# PhoenicianClock_d.net
KiCad netlist of a schematic drawn in EAGLE
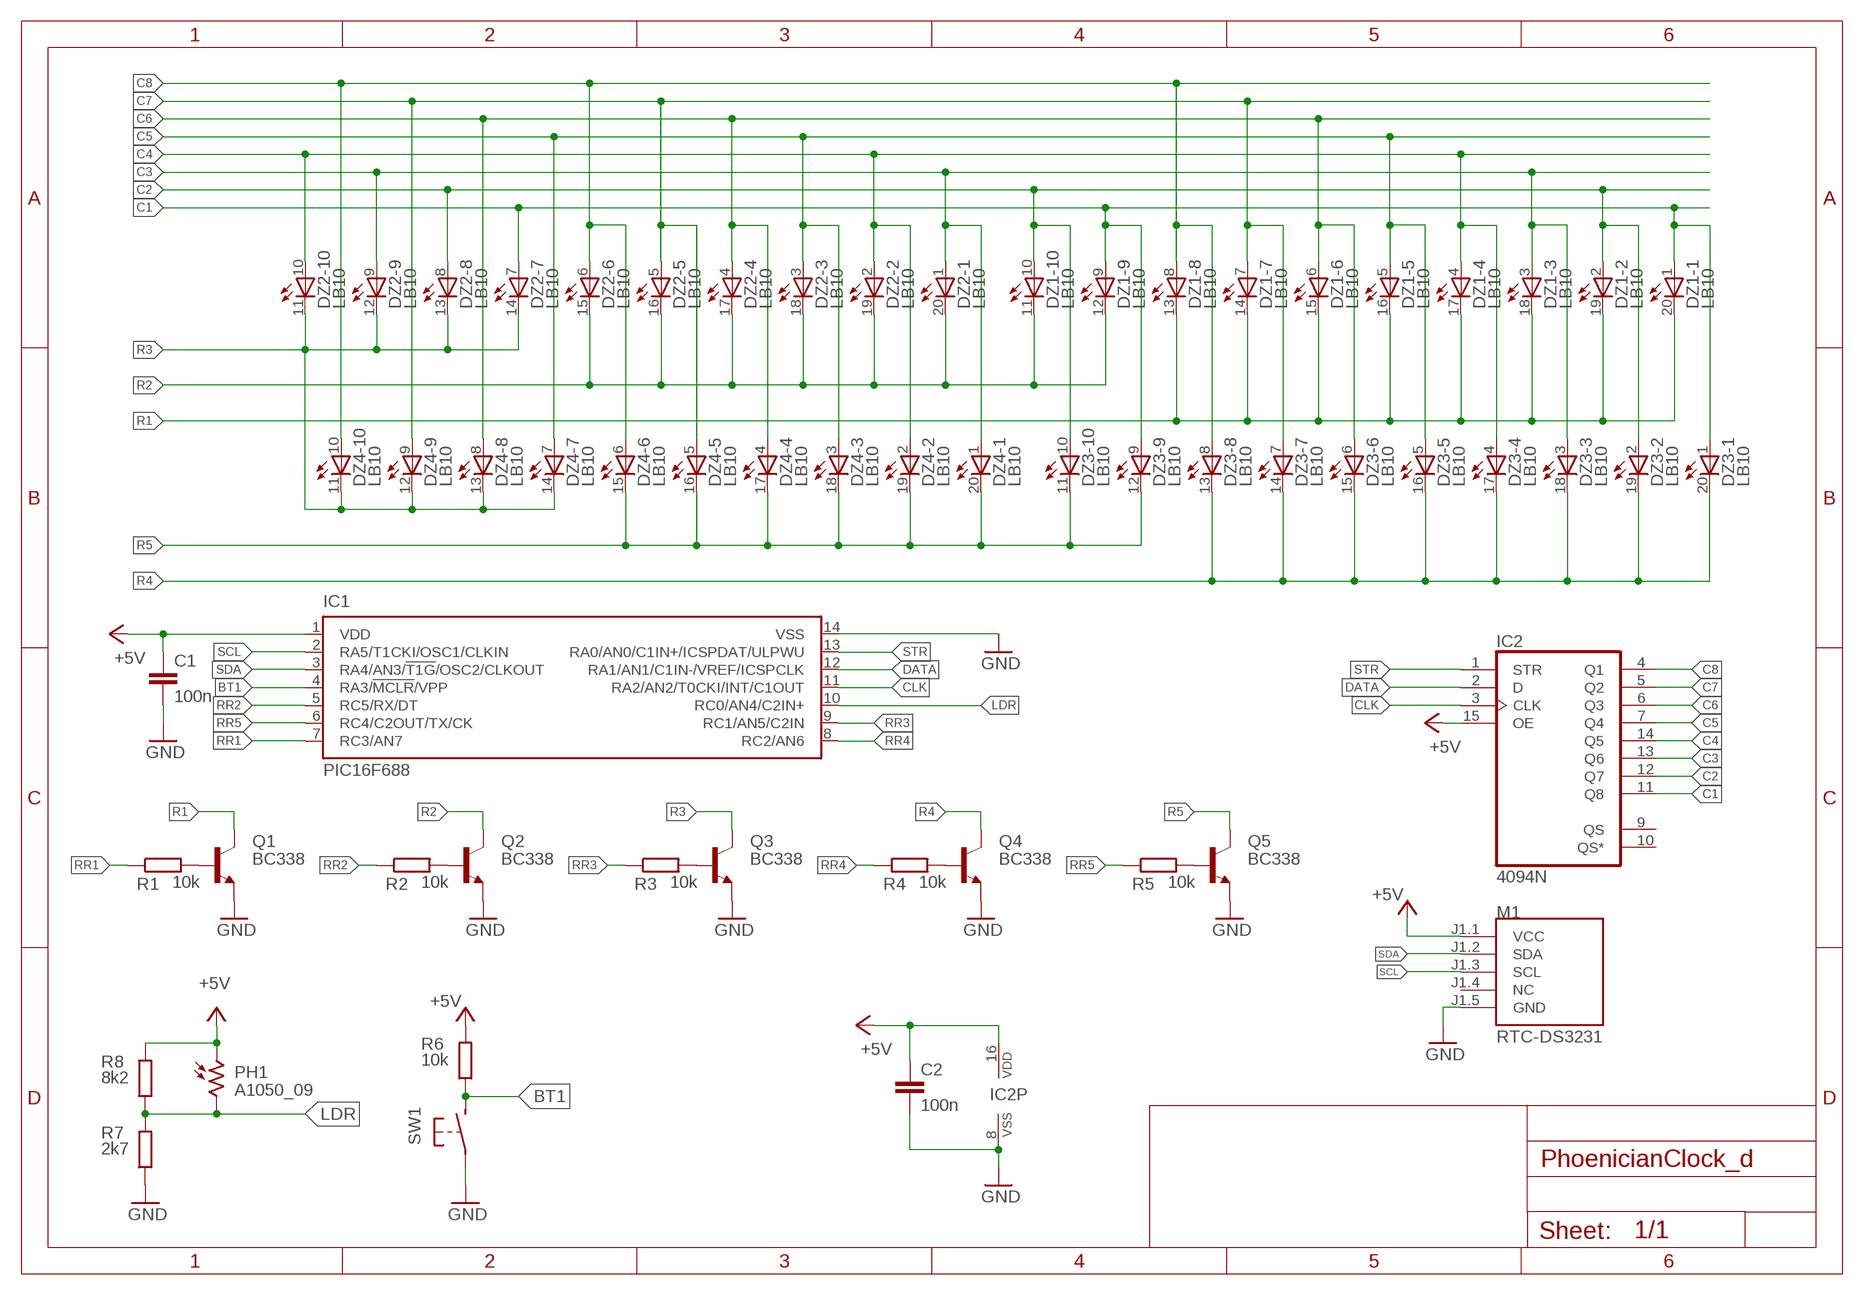
[diagram p0: schematic, sheet 1]

(export (version "E")
  (design (tool "Eeschema 10.0.6"))
  (components
    (comp (ref "C1")
      (value "100n")
      (footprint "eagle-import:C050-024X044")
      (libsource (lib "eagle-import") (part "C-EU050-024X044"))
    )
    (comp (ref "C2")
      (value "100n")
      (footprint "eagle-import:C050-024X044")
      (libsource (lib "eagle-import") (part "C-EU050-024X044"))
    )
    (comp (ref "DZ1")
      (value "LB10")
      (footprint "eagle-import:LB10")
      (libsource (lib "eagle-import") (part "LB10"))
    )
    (comp (ref "DZ2")
      (value "LB10")
      (footprint "eagle-import:LB10")
      (libsource (lib "eagle-import") (part "LB10"))
    )
    (comp (ref "DZ3")
      (value "LB10")
      (footprint "eagle-import:LB10")
      (libsource (lib "eagle-import") (part "LB10"))
    )
    (comp (ref "DZ4")
      (value "LB10")
      (footprint "eagle-import:LB10")
      (libsource (lib "eagle-import") (part "LB10"))
    )
    (comp (ref "IC1")
      (value "PIC16F688")
      (footprint "eagle-import:DIL14")
      (libsource (lib "eagle-import") (part "PIC16F688"))
    )
    (comp (ref "IC2")
      (value "4094N")
      (footprint "eagle-import:DIL16")
      (libsource (lib "eagle-import") (part "4094N"))
    )
    (comp (ref "M1")
      (value "RTC-DS3231")
      (footprint "eagle-import:RTC-DS3231_SMALL")
      (libsource (lib "eagle-import") (part "RTC-DS3231"))
    )
    (comp (ref "PH1")
      (value "A1050_09")
      (footprint "eagle-import:T0-46-A10XX")
      (libsource (lib "eagle-import") (part "A1050_09"))
    )
    (comp (ref "Q1")
      (value "BC338")
      (footprint "eagle-import:TO92-EBC")
      (libsource (lib "eagle-import") (part "BC338"))
    )
    (comp (ref "Q2")
      (value "BC338")
      (footprint "eagle-import:TO92-EBC")
      (libsource (lib "eagle-import") (part "BC338"))
    )
    (comp (ref "Q3")
      (value "BC338")
      (footprint "eagle-import:TO92-EBC")
      (libsource (lib "eagle-import") (part "BC338"))
    )
    (comp (ref "Q4")
      (value "BC338")
      (footprint "eagle-import:TO92-EBC")
      (libsource (lib "eagle-import") (part "BC338"))
    )
    (comp (ref "Q5")
      (value "BC338")
      (footprint "eagle-import:TO92-EBC")
      (libsource (lib "eagle-import") (part "BC338"))
    )
    (comp (ref "R1")
      (value "10k")
      (footprint "eagle-import:0204_5")
      (libsource (lib "eagle-import") (part "R-EU_0204/5"))
    )
    (comp (ref "R2")
      (value "10k")
      (footprint "eagle-import:0204_5")
      (libsource (lib "eagle-import") (part "R-EU_0204/5"))
    )
    (comp (ref "R3")
      (value "10k")
      (footprint "eagle-import:0204_5")
      (libsource (lib "eagle-import") (part "R-EU_0204/5"))
    )
    (comp (ref "R4")
      (value "10k")
      (footprint "eagle-import:0204_5")
      (libsource (lib "eagle-import") (part "R-EU_0204/5"))
    )
    (comp (ref "R5")
      (value "10k")
      (footprint "eagle-import:0204_5")
      (libsource (lib "eagle-import") (part "R-EU_0204/5"))
    )
    (comp (ref "R6")
      (value "10k")
      (footprint "eagle-import:0204_5")
      (libsource (lib "eagle-import") (part "R-EU_0204/5"))
    )
    (comp (ref "R7")
      (value "2k7")
      (footprint "eagle-import:0204_5")
      (libsource (lib "eagle-import") (part "R-EU_0204/5"))
    )
    (comp (ref "R8")
      (value "8k2")
      (footprint "eagle-import:0204_5")
      (libsource (lib "eagle-import") (part "R-EU_0204/5"))
    )
    (comp (ref "SW1")
      (value "MINISPDT")
      (footprint "eagle-import:2PST_MINI")
      (libsource (lib "eagle-import") (part "MINISPDT"))
    )
  )
  (nets
    (net (code "1") (name "+5V") (class "Default")
      (node (ref "C1") (pin "1") (pinfunction "1_1") (pintype "passive"))
      (node (ref "C2") (pin "1") (pinfunction "1_1") (pintype "passive"))
      (node (ref "IC1") (pin "1") (pinfunction "VDD_1") (pintype "power_in"))
      (node (ref "IC2") (pin "15") (pinfunction "OE_15") (pintype "input"))
      (node (ref "IC2") (pin "16") (pinfunction "VDD_16") (pintype "power_in"))
      (node (ref "M1") (pin "J1.1") (pinfunction "VCC_J1.1") (pintype "power_in"))
      (node (ref "PH1") (pin "1") (pinfunction "1_1") (pintype "passive"))
      (node (ref "R6") (pin "2") (pinfunction "2_2") (pintype "passive"))
      (node (ref "R8") (pin "2") (pinfunction "2_2") (pintype "passive"))
    )
    (net (code "2") (name "BT1") (class "Default")
      (node (ref "IC1") (pin "4") (pinfunction "RA3/~{MCLR}/VPP_4") (pintype "bidirectional"))
      (node (ref "R6") (pin "1") (pinfunction "1_1") (pintype "passive"))
      (node (ref "SW1") (pin "P$2") (pinfunction "S_P$2") (pintype "passive"))
    )
    (net (code "3") (name "C1") (class "Default")
      (node (ref "DZ1") (pin "1") (pinfunction "A_1") (pintype "passive"))
      (node (ref "DZ1") (pin "9") (pinfunction "A_9") (pintype "passive"))
      (node (ref "DZ2") (pin "7") (pinfunction "A_7") (pintype "passive"))
      (node (ref "DZ3") (pin "1") (pinfunction "A_1") (pintype "passive"))
      (node (ref "DZ3") (pin "9") (pinfunction "A_9") (pintype "passive"))
      (node (ref "IC2") (pin "11") (pinfunction "Q8_11") (pintype "output"))
    )
    (net (code "4") (name "C2") (class "Default")
      (node (ref "DZ1") (pin "10") (pinfunction "A_10") (pintype "passive"))
      (node (ref "DZ1") (pin "2") (pinfunction "A_2") (pintype "passive"))
      (node (ref "DZ2") (pin "8") (pinfunction "A_8") (pintype "passive"))
      (node (ref "DZ3") (pin "10") (pinfunction "A_10") (pintype "passive"))
      (node (ref "DZ3") (pin "2") (pinfunction "A_2") (pintype "passive"))
      (node (ref "IC2") (pin "12") (pinfunction "Q7_12") (pintype "output"))
    )
    (net (code "5") (name "C3") (class "Default")
      (node (ref "DZ1") (pin "3") (pinfunction "A_3") (pintype "passive"))
      (node (ref "DZ2") (pin "1") (pinfunction "A_1") (pintype "passive"))
      (node (ref "DZ2") (pin "9") (pinfunction "A_9") (pintype "passive"))
      (node (ref "DZ3") (pin "3") (pinfunction "A_3") (pintype "passive"))
      (node (ref "DZ4") (pin "1") (pinfunction "A_1") (pintype "passive"))
      (node (ref "IC2") (pin "13") (pinfunction "Q6_13") (pintype "output"))
    )
    (net (code "6") (name "C4") (class "Default")
      (node (ref "DZ1") (pin "4") (pinfunction "A_4") (pintype "passive"))
      (node (ref "DZ2") (pin "10") (pinfunction "A_10") (pintype "passive"))
      (node (ref "DZ2") (pin "2") (pinfunction "A_2") (pintype "passive"))
      (node (ref "DZ3") (pin "4") (pinfunction "A_4") (pintype "passive"))
      (node (ref "DZ4") (pin "2") (pinfunction "A_2") (pintype "passive"))
      (node (ref "IC2") (pin "14") (pinfunction "Q5_14") (pintype "output"))
    )
    (net (code "7") (name "C5") (class "Default")
      (node (ref "DZ1") (pin "5") (pinfunction "A_5") (pintype "passive"))
      (node (ref "DZ2") (pin "3") (pinfunction "A_3") (pintype "passive"))
      (node (ref "DZ3") (pin "5") (pinfunction "A_5") (pintype "passive"))
      (node (ref "DZ4") (pin "3") (pinfunction "A_3") (pintype "passive"))
      (node (ref "DZ4") (pin "7") (pinfunction "A_7") (pintype "passive"))
      (node (ref "IC2") (pin "7") (pinfunction "Q4_7") (pintype "output"))
    )
    (net (code "8") (name "C6") (class "Default")
      (node (ref "DZ1") (pin "6") (pinfunction "A_6") (pintype "passive"))
      (node (ref "DZ2") (pin "4") (pinfunction "A_4") (pintype "passive"))
      (node (ref "DZ3") (pin "6") (pinfunction "A_6") (pintype "passive"))
      (node (ref "DZ4") (pin "4") (pinfunction "A_4") (pintype "passive"))
      (node (ref "DZ4") (pin "8") (pinfunction "A_8") (pintype "passive"))
      (node (ref "IC2") (pin "6") (pinfunction "Q3_6") (pintype "output"))
    )
    (net (code "9") (name "C7") (class "Default")
      (node (ref "DZ1") (pin "7") (pinfunction "A_7") (pintype "passive"))
      (node (ref "DZ2") (pin "5") (pinfunction "A_5") (pintype "passive"))
      (node (ref "DZ3") (pin "7") (pinfunction "A_7") (pintype "passive"))
      (node (ref "DZ4") (pin "5") (pinfunction "A_5") (pintype "passive"))
      (node (ref "DZ4") (pin "9") (pinfunction "A_9") (pintype "passive"))
      (node (ref "IC2") (pin "5") (pinfunction "Q2_5") (pintype "output"))
    )
    (net (code "10") (name "C8") (class "Default")
      (node (ref "DZ1") (pin "8") (pinfunction "A_8") (pintype "passive"))
      (node (ref "DZ2") (pin "6") (pinfunction "A_6") (pintype "passive"))
      (node (ref "DZ3") (pin "8") (pinfunction "A_8") (pintype "passive"))
      (node (ref "DZ4") (pin "10") (pinfunction "A_10") (pintype "passive"))
      (node (ref "DZ4") (pin "6") (pinfunction "A_6") (pintype "passive"))
      (node (ref "IC2") (pin "4") (pinfunction "Q1_4") (pintype "output"))
    )
    (net (code "11") (name "CLK") (class "Default")
      (node (ref "IC1") (pin "11") (pinfunction "RA2/AN2/T0CKI/INT/C1OUT_11") (pintype "bidirectional"))
      (node (ref "IC2") (pin "3") (pinfunction "CLK_3") (pintype "input"))
    )
    (net (code "12") (name "DATA") (class "Default")
      (node (ref "IC1") (pin "12") (pinfunction "RA1/AN1/C1IN-/VREF/ICSPCLK_12") (pintype "bidirectional"))
      (node (ref "IC2") (pin "2") (pinfunction "D_2") (pintype "input"))
    )
    (net (code "13") (name "GND") (class "Default")
      (node (ref "C1") (pin "2") (pinfunction "2_2") (pintype "passive"))
      (node (ref "C2") (pin "2") (pinfunction "2_2") (pintype "passive"))
      (node (ref "IC1") (pin "14") (pinfunction "VSS_14") (pintype "power_in"))
      (node (ref "IC2") (pin "8") (pinfunction "VSS_8") (pintype "power_in"))
      (node (ref "M1") (pin "J1.5") (pinfunction "GND_J1.5") (pintype "power_in"))
      (node (ref "Q1") (pin "E") (pinfunction "E_E") (pintype "passive"))
      (node (ref "Q2") (pin "E") (pinfunction "E_E") (pintype "passive"))
      (node (ref "Q3") (pin "E") (pinfunction "E_E") (pintype "passive"))
      (node (ref "Q4") (pin "E") (pinfunction "E_E") (pintype "passive"))
      (node (ref "Q5") (pin "E") (pinfunction "E_E") (pintype "passive"))
      (node (ref "R7") (pin "1") (pinfunction "1_1") (pintype "passive"))
      (node (ref "SW1") (pin "P$1") (pinfunction "P_P$1") (pintype "passive"))
    )
    (net (code "14") (name "LDR") (class "Default")
      (node (ref "IC1") (pin "10") (pinfunction "RC0/AN4/C2IN+_10") (pintype "bidirectional"))
      (node (ref "PH1") (pin "2") (pinfunction "2_2") (pintype "passive"))
      (node (ref "R7") (pin "2") (pinfunction "2_2") (pintype "passive"))
      (node (ref "R8") (pin "1") (pinfunction "1_1") (pintype "passive"))
    )
    (net (code "15") (name "Net-(Q1-PadB)") (class "Default")
      (node (ref "Q1") (pin "B") (pinfunction "B_B") (pintype "passive"))
      (node (ref "R1") (pin "2") (pinfunction "2_2") (pintype "passive"))
    )
    (net (code "16") (name "Net-(Q2-PadB)") (class "Default")
      (node (ref "Q2") (pin "B") (pinfunction "B_B") (pintype "passive"))
      (node (ref "R2") (pin "2") (pinfunction "2_2") (pintype "passive"))
    )
    (net (code "17") (name "Net-(Q3-PadB)") (class "Default")
      (node (ref "Q3") (pin "B") (pinfunction "B_B") (pintype "passive"))
      (node (ref "R3") (pin "2") (pinfunction "2_2") (pintype "passive"))
    )
    (net (code "18") (name "Net-(Q4-PadB)") (class "Default")
      (node (ref "Q4") (pin "B") (pinfunction "B_B") (pintype "passive"))
      (node (ref "R4") (pin "2") (pinfunction "2_2") (pintype "passive"))
    )
    (net (code "19") (name "Net-(Q5-PadB)") (class "Default")
      (node (ref "Q5") (pin "B") (pinfunction "B_B") (pintype "passive"))
      (node (ref "R5") (pin "2") (pinfunction "2_2") (pintype "passive"))
    )
    (net (code "20") (name "R1") (class "Default")
      (node (ref "DZ1") (pin "13") (pinfunction "C_13") (pintype "passive"))
      (node (ref "DZ1") (pin "14") (pinfunction "C_14") (pintype "passive"))
      (node (ref "DZ1") (pin "15") (pinfunction "C_15") (pintype "passive"))
      (node (ref "DZ1") (pin "16") (pinfunction "C_16") (pintype "passive"))
      (node (ref "DZ1") (pin "17") (pinfunction "C_17") (pintype "passive"))
      (node (ref "DZ1") (pin "18") (pinfunction "C_18") (pintype "passive"))
      (node (ref "DZ1") (pin "19") (pinfunction "C_19") (pintype "passive"))
      (node (ref "DZ1") (pin "20") (pinfunction "C_20") (pintype "passive"))
      (node (ref "Q1") (pin "C") (pinfunction "C_C") (pintype "passive"))
    )
    (net (code "21") (name "R2") (class "Default")
      (node (ref "DZ1") (pin "11") (pinfunction "C_11") (pintype "passive"))
      (node (ref "DZ1") (pin "12") (pinfunction "C_12") (pintype "passive"))
      (node (ref "DZ2") (pin "15") (pinfunction "C_15") (pintype "passive"))
      (node (ref "DZ2") (pin "16") (pinfunction "C_16") (pintype "passive"))
      (node (ref "DZ2") (pin "17") (pinfunction "C_17") (pintype "passive"))
      (node (ref "DZ2") (pin "18") (pinfunction "C_18") (pintype "passive"))
      (node (ref "DZ2") (pin "19") (pinfunction "C_19") (pintype "passive"))
      (node (ref "DZ2") (pin "20") (pinfunction "C_20") (pintype "passive"))
      (node (ref "Q2") (pin "C") (pinfunction "C_C") (pintype "passive"))
    )
    (net (code "22") (name "R3") (class "Default")
      (node (ref "DZ2") (pin "11") (pinfunction "C_11") (pintype "passive"))
      (node (ref "DZ2") (pin "12") (pinfunction "C_12") (pintype "passive"))
      (node (ref "DZ2") (pin "13") (pinfunction "C_13") (pintype "passive"))
      (node (ref "DZ2") (pin "14") (pinfunction "C_14") (pintype "passive"))
      (node (ref "DZ4") (pin "11") (pinfunction "C_11") (pintype "passive"))
      (node (ref "DZ4") (pin "12") (pinfunction "C_12") (pintype "passive"))
      (node (ref "DZ4") (pin "13") (pinfunction "C_13") (pintype "passive"))
      (node (ref "DZ4") (pin "14") (pinfunction "C_14") (pintype "passive"))
      (node (ref "Q3") (pin "C") (pinfunction "C_C") (pintype "passive"))
    )
    (net (code "23") (name "R4") (class "Default")
      (node (ref "DZ3") (pin "13") (pinfunction "C_13") (pintype "passive"))
      (node (ref "DZ3") (pin "14") (pinfunction "C_14") (pintype "passive"))
      (node (ref "DZ3") (pin "15") (pinfunction "C_15") (pintype "passive"))
      (node (ref "DZ3") (pin "16") (pinfunction "C_16") (pintype "passive"))
      (node (ref "DZ3") (pin "17") (pinfunction "C_17") (pintype "passive"))
      (node (ref "DZ3") (pin "18") (pinfunction "C_18") (pintype "passive"))
      (node (ref "DZ3") (pin "19") (pinfunction "C_19") (pintype "passive"))
      (node (ref "DZ3") (pin "20") (pinfunction "C_20") (pintype "passive"))
      (node (ref "Q4") (pin "C") (pinfunction "C_C") (pintype "passive"))
    )
    (net (code "24") (name "R5") (class "Default")
      (node (ref "DZ3") (pin "11") (pinfunction "C_11") (pintype "passive"))
      (node (ref "DZ3") (pin "12") (pinfunction "C_12") (pintype "passive"))
      (node (ref "DZ4") (pin "15") (pinfunction "C_15") (pintype "passive"))
      (node (ref "DZ4") (pin "16") (pinfunction "C_16") (pintype "passive"))
      (node (ref "DZ4") (pin "17") (pinfunction "C_17") (pintype "passive"))
      (node (ref "DZ4") (pin "18") (pinfunction "C_18") (pintype "passive"))
      (node (ref "DZ4") (pin "19") (pinfunction "C_19") (pintype "passive"))
      (node (ref "DZ4") (pin "20") (pinfunction "C_20") (pintype "passive"))
      (node (ref "Q5") (pin "C") (pinfunction "C_C") (pintype "passive"))
    )
    (net (code "25") (name "RR1") (class "Default")
      (node (ref "IC1") (pin "7") (pinfunction "RC3/AN7_7") (pintype "bidirectional"))
      (node (ref "R1") (pin "1") (pinfunction "1_1") (pintype "passive"))
    )
    (net (code "26") (name "RR2") (class "Default")
      (node (ref "IC1") (pin "5") (pinfunction "RC5/RX/DT_5") (pintype "bidirectional"))
      (node (ref "R2") (pin "1") (pinfunction "1_1") (pintype "passive"))
    )
    (net (code "27") (name "RR3") (class "Default")
      (node (ref "IC1") (pin "9") (pinfunction "RC1/AN5/C2IN_9") (pintype "bidirectional"))
      (node (ref "R3") (pin "1") (pinfunction "1_1") (pintype "passive"))
    )
    (net (code "28") (name "RR4") (class "Default")
      (node (ref "IC1") (pin "8") (pinfunction "RC2/AN6_8") (pintype "bidirectional"))
      (node (ref "R4") (pin "1") (pinfunction "1_1") (pintype "passive"))
    )
    (net (code "29") (name "RR5") (class "Default")
      (node (ref "IC1") (pin "6") (pinfunction "RC4/C2OUT/TX/CK_6") (pintype "bidirectional"))
      (node (ref "R5") (pin "1") (pinfunction "1_1") (pintype "passive"))
    )
    (net (code "30") (name "SCL") (class "Default")
      (node (ref "IC1") (pin "2") (pinfunction "RA5/T1CKI/OSC1/CLKIN_2") (pintype "input"))
      (node (ref "M1") (pin "J1.3") (pinfunction "SCL_J1.3") (pintype "bidirectional"))
    )
    (net (code "31") (name "SDA") (class "Default")
      (node (ref "IC1") (pin "3") (pinfunction "RA4/AN3/~{T1G}/OSC2/CLKOUT_3") (pintype "bidirectional"))
      (node (ref "M1") (pin "J1.2") (pinfunction "SDA_J1.2") (pintype "bidirectional"))
    )
    (net (code "32") (name "STR") (class "Default")
      (node (ref "IC1") (pin "13") (pinfunction "RA0/AN0/C1IN+/ICSPDAT/ULPWU_13") (pintype "bidirectional"))
      (node (ref "IC2") (pin "1") (pinfunction "STR_1") (pintype "input"))
    )
    (net (code "33") (name "unconnected-(IC2A-QS*-Pad10)") (class "Default")
      (node (ref "IC2") (pin "10") (pinfunction "QS*_10") (pintype "output"))
    )
    (net (code "34") (name "unconnected-(IC2A-QS-Pad9)") (class "Default")
      (node (ref "IC2") (pin "9") (pinfunction "QS_9") (pintype "output"))
    )
    (net (code "35") (name "unconnected-(M1-NC-PadJ1.4)") (class "Default")
      (node (ref "M1") (pin "J1.4") (pinfunction "NC_J1.4") (pintype "bidirectional"))
    )
  )
)
